# tube_pcb.net
KiCad netlist of a schematic drawn in EAGLE
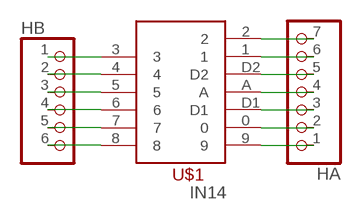
[diagram p0: schematic, sheet 1]

(export (version "E")
  (design (tool "Eeschema 10.0.6"))
  (components
    (comp (ref "HA")
      (value "PINHD-1X7")
      (footprint "eagle-import:1X07")
      (libsource (lib "eagle-import") (part "PINHD-1X7"))
    )
    (comp (ref "HB")
      (value "PINHD-1X6")
      (footprint "eagle-import:1X06")
      (libsource (lib "eagle-import") (part "PINHD-1X6"))
    )
    (comp (ref "U$1")
      (value "IN14")
      (footprint "eagle-import:IN14")
      (libsource (lib "eagle-import") (part "IN14"))
    )
  )
  (nets
    (net (code "1") (name "Net-(HA-Pad1)") (class "Default")
      (node (ref "HA") (pin "1") (pinfunction "1_1") (pintype "passive"))
      (node (ref "U$1") (pin "9") (pinfunction "9_9") (pintype "bidirectional"))
    )
    (net (code "2") (name "Net-(HA-Pad2)") (class "Default")
      (node (ref "HA") (pin "2") (pinfunction "2_2") (pintype "passive"))
      (node (ref "U$1") (pin "0") (pinfunction "0_0") (pintype "bidirectional"))
    )
    (net (code "3") (name "Net-(HA-Pad3)") (class "Default")
      (node (ref "HA") (pin "3") (pinfunction "3_3") (pintype "passive"))
      (node (ref "U$1") (pin "D1") (pinfunction "D1_D1") (pintype "bidirectional"))
    )
    (net (code "4") (name "Net-(HA-Pad4)") (class "Default")
      (node (ref "HA") (pin "4") (pinfunction "4_4") (pintype "passive"))
      (node (ref "U$1") (pin "A") (pinfunction "A_A") (pintype "bidirectional"))
    )
    (net (code "5") (name "Net-(HA-Pad5)") (class "Default")
      (node (ref "HA") (pin "5") (pinfunction "5_5") (pintype "passive"))
      (node (ref "U$1") (pin "D2") (pinfunction "D2_D2") (pintype "bidirectional"))
    )
    (net (code "6") (name "Net-(HA-Pad6)") (class "Default")
      (node (ref "HA") (pin "6") (pinfunction "6_6") (pintype "passive"))
      (node (ref "U$1") (pin "1") (pinfunction "1_1") (pintype "bidirectional"))
    )
    (net (code "7") (name "Net-(HA-Pad7)") (class "Default")
      (node (ref "HA") (pin "7") (pinfunction "7_7") (pintype "passive"))
      (node (ref "U$1") (pin "2") (pinfunction "2_2") (pintype "bidirectional"))
    )
    (net (code "8") (name "Net-(HB-Pad1)") (class "Default")
      (node (ref "HB") (pin "1") (pinfunction "1_1") (pintype "passive"))
      (node (ref "U$1") (pin "3") (pinfunction "3_3") (pintype "bidirectional"))
    )
    (net (code "9") (name "Net-(HB-Pad2)") (class "Default")
      (node (ref "HB") (pin "2") (pinfunction "2_2") (pintype "passive"))
      (node (ref "U$1") (pin "4") (pinfunction "4_4") (pintype "bidirectional"))
    )
    (net (code "10") (name "Net-(HB-Pad3)") (class "Default")
      (node (ref "HB") (pin "3") (pinfunction "3_3") (pintype "passive"))
      (node (ref "U$1") (pin "5") (pinfunction "5_5") (pintype "bidirectional"))
    )
    (net (code "11") (name "Net-(HB-Pad4)") (class "Default")
      (node (ref "HB") (pin "4") (pinfunction "4_4") (pintype "passive"))
      (node (ref "U$1") (pin "6") (pinfunction "6_6") (pintype "bidirectional"))
    )
    (net (code "12") (name "Net-(HB-Pad5)") (class "Default")
      (node (ref "HB") (pin "5") (pinfunction "5_5") (pintype "passive"))
      (node (ref "U$1") (pin "7") (pinfunction "7_7") (pintype "bidirectional"))
    )
    (net (code "13") (name "Net-(HB-Pad6)") (class "Default")
      (node (ref "HB") (pin "6") (pinfunction "6_6") (pintype "passive"))
      (node (ref "U$1") (pin "8") (pinfunction "8_8") (pintype "bidirectional"))
    )
  )
)
